# ScopePower.net
KiCad netlist of a schematic drawn in Altium Designer
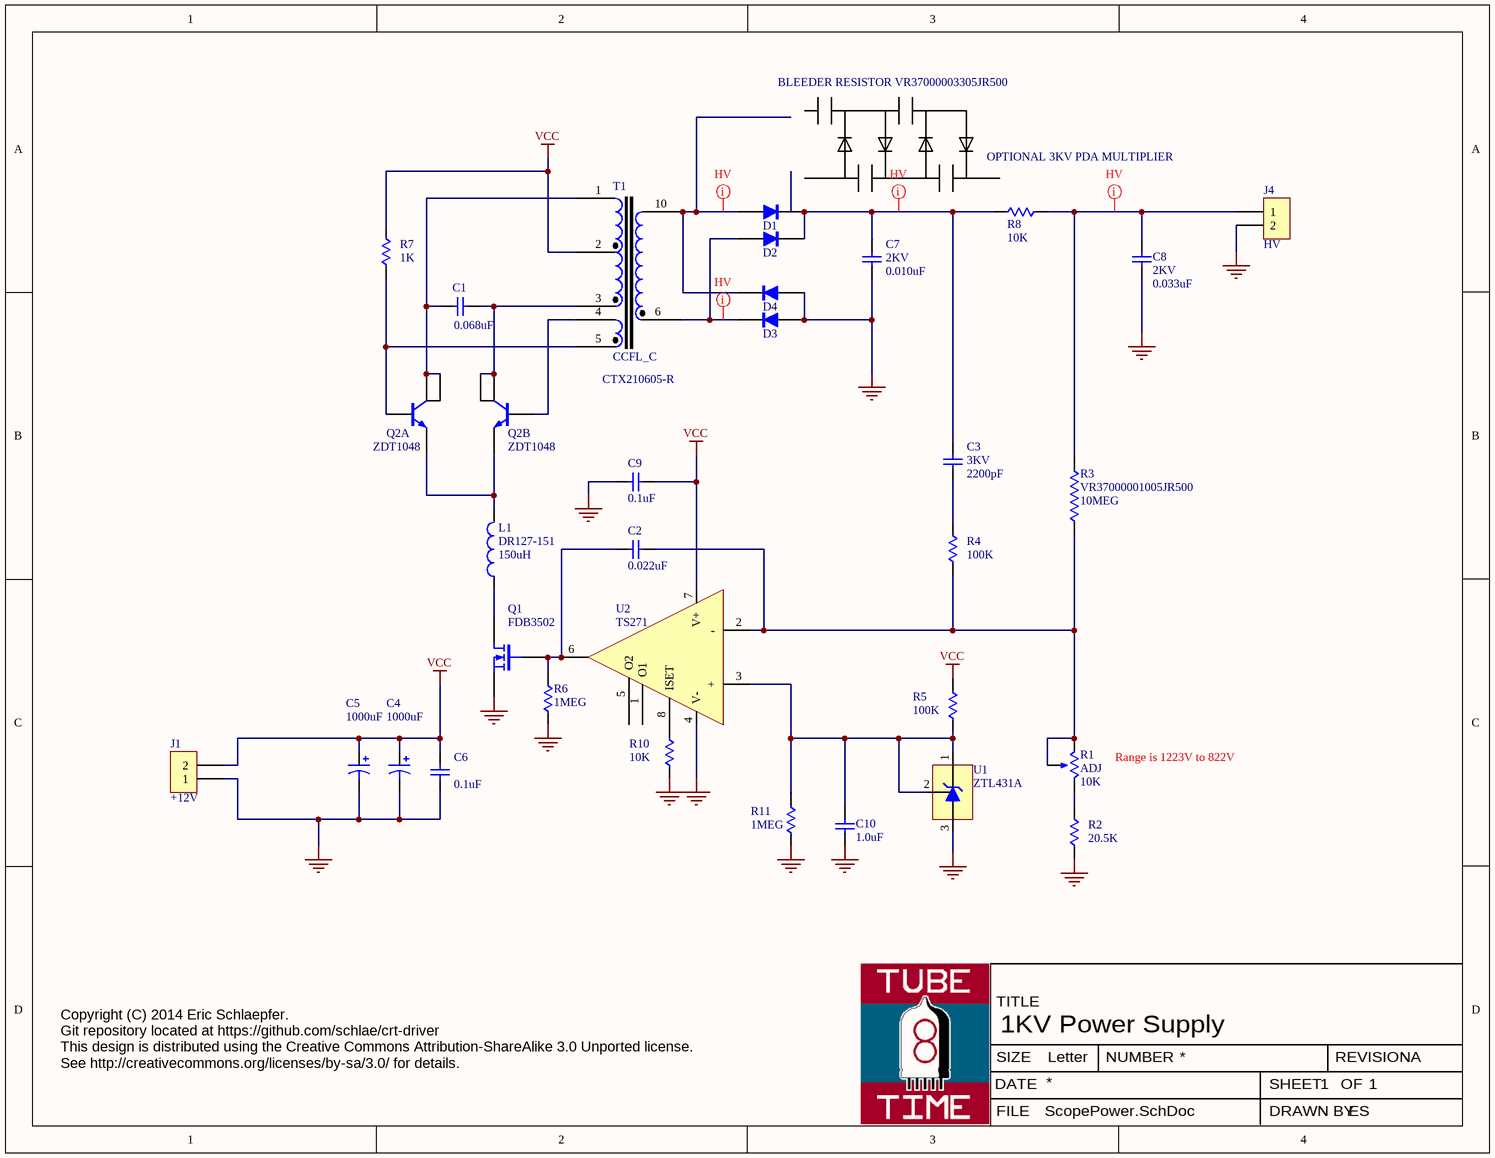
[diagram p0: ScopePower.SchDoc]

(export (version "E")
  (design (tool "Eeschema 10.0.6"))
  (components
    (comp (ref "C1")
      (value "0.068uF")
      (footprint "WIMAMKP2")
      (description "Capacitor")
      (fields (field (name "MANUFPART") "MKP2D026801E00JSSD") (field (name "Comment") "Cap"))
      (libsource (lib "ClikCommon") (part "Cap"))
    )
    (comp (ref "C2")
      (value "0.022uF")
      (footprint "G_0805[2012]")
      (description "Capacitor")
      (libsource (lib "ClikCommon") (part "Cap"))
    )
    (comp (ref "C3")
      (value "3KV")
      (footprint "CAP250X100")
      (description "Capacitor")
      (fields (field (name "ALTIUM_VALUE") "2200pF") (field (name "MANUFPART") "564R30GAD22"))
      (libsource (lib "ClikCommon") (part "Cap"))
    )
    (comp (ref "C4")
      (value "1000uF")
      (footprint "CAP_R200x400")
      (description "Polarized Capacitor")
      (fields (field (name "MANUFPART") "UVR1E102MPD") (field (name "Comment") "Cap Pol2"))
      (libsource (lib "ClikCommon") (part "CapP"))
    )
    (comp (ref "C5")
      (value "1000uF")
      (footprint "CAP_R200x400")
      (description "Polarized Capacitor")
      (fields (field (name "MANUFPART") "UVR1E102MPD") (field (name "Comment") "Cap Pol2"))
      (libsource (lib "ClikCommon") (part "CapP"))
    )
    (comp (ref "C6")
      (value "0.1uF")
      (footprint "G_0805[2012]")
      (description "Capacitor")
      (libsource (lib "ClikCommon") (part "Cap"))
    )
    (comp (ref "C7")
      (value "2KV")
      (footprint "CAP400X100")
      (description "Capacitor")
      (fields (field (name "ALTIUM_VALUE") "0.010uF") (field (name "MANUFPART") "564R20GASS10"))
      (libsource (lib "ClikCommon") (part "Cap"))
    )
    (comp (ref "C8")
      (value "2KV")
      (footprint "CAP400X100")
      (description "Capacitor")
      (fields (field (name "ALTIUM_VALUE") "0.033uF") (field (name "MANUFPART") "565R30GASS33"))
      (libsource (lib "ClikCommon") (part "Cap"))
    )
    (comp (ref "C9")
      (value "0.1uF")
      (footprint "G_0805[2012]")
      (description "Capacitor")
      (libsource (lib "ClikCommon") (part "Cap"))
    )
    (comp (ref "C10")
      (value "1.0uF")
      (footprint "G_0805[2012]")
      (description "Capacitor")
      (fields (field (name "MANUFPART") "C2012X7R1E105K125AB") (field (name "Comment") "Cap"))
      (libsource (lib "ClikCommon") (part "Cap"))
    )
    (comp (ref "D1")
      (value "Diode")
      (footprint "DIODE400X100")
      (fields (field (name "MANUFPART") "rgp02-20e"))
      (libsource (lib "ClikCommon") (part "Diode"))
    )
    (comp (ref "D2")
      (value "Diode")
      (footprint "DIODE400X100")
      (fields (field (name "MANUFPART") "rgp02-20e"))
      (libsource (lib "ClikCommon") (part "Diode"))
    )
    (comp (ref "D3")
      (value "Diode")
      (footprint "DIODE400X100")
      (fields (field (name "MANUFPART") "rgp02-20e"))
      (libsource (lib "") (part "Diode_1"))
    )
    (comp (ref "D4")
      (value "Diode")
      (footprint "DIODE400X100")
      (fields (field (name "MANUFPART") "rgp02-20e"))
      (libsource (lib "") (part "Diode_1"))
    )
    (comp (ref "J1")
      (value "+12V")
      (footprint "HDR2S156")
      (description "Connector, 2 pin")
      (libsource (lib "") (part "CON2_1"))
    )
    (comp (ref "J4")
      (value "HV")
      (footprint "HDR3S156M1")
      (description "Connector, 2 pin")
      (libsource (lib "ClikConnectors") (part "CON2"))
    )
    (comp (ref "L1")
      (value "DR127-151")
      (footprint "DR124")
      (description "Inductor")
      (fields (field (name "ALTIUM_VALUE") "150uH") (field (name "MANUFPART") "DR127-151-R"))
      (libsource (lib "ClikCommon") (part "Inductor"))
    )
    (comp (ref "Q1")
      (value "FDB3502")
      (footprint "G_TO252M[D2PAK]")
      (description "N-Channel MOSFET")
      (libsource (lib "ClikCommon") (part "MOSFET-N"))
    )
    (comp (ref "Q2")
      (value "ZDT1048")
      (footprint "G_SOT223-8")
      (description "NPN Dual Bipolar Transistor")
      (fields (field (name "MANUFPART") "ZDT1048TA"))
      (libsource (lib "ClikCommon") (part "NPN_DUAL"))
    )
    (comp (ref "R1")
      (value "ADJ")
      (footprint "POT_TRIM BOURNS 3386F")
      (description "Variable Resistor")
      (fields (field (name "ALTIUM_VALUE") "10K") (field (name "MANUFPART") "3386F-1-103LF"))
      (libsource (lib "ClikCommon") (part "Pot"))
    )
    (comp (ref "R2")
      (value "20.5K")
      (footprint "G_0805[2012]")
      (description "Resistor")
      (fields (field (name "MANUFPART") "CRCW080520K5FKEA") (field (name "Comment") "Res1"))
      (libsource (lib "ClikCommon") (part "Res"))
    )
    (comp (ref "R3")
      (value "VR37000001005JR500")
      (footprint "RES500X160")
      (description "Resistor, Special Property")
      (fields (field (name "ALTIUM_VALUE") "10MEG"))
      (libsource (lib "ClikCommon") (part "ResSpecial"))
    )
    (comp (ref "R4")
      (value "100K")
      (footprint "G_1206[3216]")
      (description "Resistor")
      (fields (field (name "MANUFPART") "CRCW1206100KFKEA"))
      (libsource (lib "ClikCommon") (part "Res"))
    )
    (comp (ref "R5")
      (value "100K")
      (footprint "G_0805[2012]")
      (description "Resistor")
      (fields (field (name "MANUFPART") "CRCW0805100KFKEA"))
      (libsource (lib "ClikCommon") (part "Res"))
    )
    (comp (ref "R6")
      (value "1MEG")
      (footprint "G_0805[2012]")
      (description "Resistor")
      (fields (field (name "MANUFPART") "CRCW08051M00FKEA"))
      (libsource (lib "ClikCommon") (part "Res"))
    )
    (comp (ref "R7")
      (value "1K")
      (footprint "G_0805[2012]")
      (description "Resistor")
      (fields (field (name "MANUFPART") "CRCW08051K00JNEA") (field (name "Comment") "Res1"))
      (libsource (lib "ClikCommon") (part "Res"))
    )
    (comp (ref "R8")
      (value "10K")
      (footprint "G_1206[3216]")
      (description "Resistor")
      (fields (field (name "MANUFPART") "CRCW120610K0FKEA") (field (name "Comment") "Res1"))
      (libsource (lib "ClikCommon") (part "Res"))
    )
    (comp (ref "R10")
      (value "10K")
      (footprint "G_0805[2012]")
      (description "Resistor")
      (fields (field (name "MANUFPART") "CRCW080510K0FKTA"))
      (libsource (lib "ClikCommon") (part "Res"))
    )
    (comp (ref "R11")
      (value "1MEG")
      (footprint "G_0805[2012]")
      (description "Resistor")
      (fields (field (name "MANUFPART") "CRCW08051M00FKEA"))
      (libsource (lib "ClikCommon") (part "Res"))
    )
    (comp (ref "T1")
      (value "CCFL_C")
      (footprint "CTX2106xx")
      (description "CCFL Transformer")
      (fields (field (name "MANUFPART") "CTX210605-R"))
      (libsource (lib "ClikCommon") (part "CCFL_C"))
    )
    (comp (ref "U1")
      (value "ZTL431A")
      (footprint "G_SOT23")
      (description "Adjustable Shunt Reg")
      (libsource (lib "ClikIC") (part "TL431"))
    )
    (comp (ref "U2")
      (value "TS271")
      (footprint "G_SO8")
      (description "Generic Single Op Amp")
      (fields (field (name "MANUFPART") "TS271IDT"))
      (libsource (lib "ClikIC") (part "OpAmpSingle"))
    )
  )
  (nets
    (net (code "1") (name "GND") (class "Default")
      (node (ref "C10") (pin "1") (pinfunction "1_1") (pintype "passive"))
      (node (ref "C4") (pin "2") (pinfunction "2_2") (pintype "passive"))
      (node (ref "C5") (pin "2") (pinfunction "2_2") (pintype "passive"))
      (node (ref "C6") (pin "2") (pinfunction "2_2") (pintype "passive"))
      (node (ref "C7") (pin "1") (pinfunction "1_1") (pintype "passive"))
      (node (ref "C8") (pin "2") (pinfunction "2_2") (pintype "passive"))
      (node (ref "C9") (pin "2") (pinfunction "2_2") (pintype "passive"))
      (node (ref "D3") (pin "A") (pinfunction "A_A") (pintype "passive"))
      (node (ref "D4") (pin "A") (pinfunction "A_A") (pintype "passive"))
      (node (ref "J1") (pin "1") (pinfunction "1_1") (pintype "passive"))
      (node (ref "J4") (pin "2") (pinfunction "2_2") (pintype "passive"))
      (node (ref "Q1") (pin "S") (pinfunction "S_S") (pintype "passive"))
      (node (ref "R10") (pin "2") (pinfunction "2_2") (pintype "passive"))
      (node (ref "R11") (pin "2") (pinfunction "2_2") (pintype "passive"))
      (node (ref "R2") (pin "1") (pinfunction "1_1") (pintype "passive"))
      (node (ref "R6") (pin "2") (pinfunction "2_2") (pintype "passive"))
      (node (ref "U1") (pin "3") (pinfunction "A_3") (pintype "passive"))
      (node (ref "U2") (pin "4") (pinfunction "V-_4") (pintype "power_in"))
    )
    (net (code "2") (name "Net-(C1-Pad1)") (class "Default")
      (node (ref "C1") (pin "1") (pinfunction "1_1") (pintype "passive"))
      (node (ref "Q2") (pin "5") (pinfunction "C_5") (pintype "passive"))
      (node (ref "Q2") (pin "6") (pinfunction "C_6") (pintype "passive"))
      (node (ref "T1") (pin "1") (pinfunction "1_1") (pintype "passive"))
    )
    (net (code "3") (name "Net-(C1-Pad2)") (class "Default")
      (node (ref "C1") (pin "2") (pinfunction "2_2") (pintype "passive"))
      (node (ref "Q2") (pin "7") (pinfunction "C_7") (pintype "passive"))
      (node (ref "Q2") (pin "8") (pinfunction "C_8") (pintype "passive"))
      (node (ref "T1") (pin "3") (pinfunction "3_3") (pintype "passive"))
    )
    (net (code "4") (name "Net-(C3-Pad1)") (class "Default")
      (node (ref "C3") (pin "1") (pinfunction "1_1") (pintype "passive"))
      (node (ref "R4") (pin "2") (pinfunction "2_2") (pintype "passive"))
    )
    (net (code "5") (name "Net-(C3-Pad2)") (class "Default")
      (node (ref "C3") (pin "2") (pinfunction "2_2") (pintype "passive"))
      (node (ref "C7") (pin "2") (pinfunction "2_2") (pintype "passive"))
      (node (ref "D1") (pin "K") (pinfunction "K_K") (pintype "passive"))
      (node (ref "D2") (pin "K") (pinfunction "K_K") (pintype "passive"))
      (node (ref "R8") (pin "1") (pinfunction "1_1") (pintype "passive"))
    )
    (net (code "6") (name "Net-(C8-Pad1)") (class "Default")
      (node (ref "C8") (pin "1") (pinfunction "1_1") (pintype "passive"))
      (node (ref "J4") (pin "1") (pinfunction "1_1") (pintype "passive"))
      (node (ref "R3") (pin "2") (pinfunction "2_2") (pintype "passive"))
      (node (ref "R8") (pin "2") (pinfunction "2_2") (pintype "passive"))
    )
    (net (code "7") (name "Net-(D1-PadA)") (class "Default")
      (node (ref "D1") (pin "A") (pinfunction "A_A") (pintype "passive"))
      (node (ref "D4") (pin "K") (pinfunction "K_K") (pintype "passive"))
      (node (ref "T1") (pin "10") (pinfunction "10_10") (pintype "passive"))
    )
    (net (code "8") (name "Net-(D2-PadA)") (class "Default")
      (node (ref "D2") (pin "A") (pinfunction "A_A") (pintype "passive"))
      (node (ref "D3") (pin "K") (pinfunction "K_K") (pintype "passive"))
      (node (ref "T1") (pin "6") (pinfunction "6_6") (pintype "passive"))
    )
    (net (code "9") (name "Net-(L1-Pad1)") (class "Default")
      (node (ref "L1") (pin "1") (pinfunction "1_1") (pintype "passive"))
      (node (ref "Q1") (pin "D") (pinfunction "D_D") (pintype "passive"))
    )
    (net (code "10") (name "Net-(Q2A-B)") (class "Default")
      (node (ref "Q2") (pin "4") (pinfunction "B_4") (pintype "passive"))
      (node (ref "R7") (pin "1") (pinfunction "1_1") (pintype "passive"))
      (node (ref "T1") (pin "5") (pinfunction "5_5") (pintype "passive"))
    )
    (net (code "11") (name "Net-(Q2A-E)") (class "Default")
      (node (ref "L1") (pin "2") (pinfunction "2_2") (pintype "passive"))
      (node (ref "Q2") (pin "1") (pinfunction "E_1") (pintype "passive"))
      (node (ref "Q2") (pin "3") (pinfunction "E_3") (pintype "passive"))
    )
    (net (code "12") (name "Net-(Q2B-B)") (class "Default")
      (node (ref "Q2") (pin "2") (pinfunction "B_2") (pintype "passive"))
      (node (ref "T1") (pin "4") (pinfunction "4_4") (pintype "passive"))
    )
    (net (code "13") (name "Net-(R1-BOT)") (class "Default")
      (node (ref "C2") (pin "1") (pinfunction "1_1") (pintype "passive"))
      (node (ref "R1") (pin "2") (pinfunction "BOT_2") (pintype "passive"))
      (node (ref "R1") (pin "3") (pinfunction "TAP_3") (pintype "passive"))
      (node (ref "R3") (pin "1") (pinfunction "1_1") (pintype "passive"))
      (node (ref "R4") (pin "1") (pinfunction "1_1") (pintype "passive"))
      (node (ref "U2") (pin "2") (pinfunction "-_2") (pintype "passive"))
    )
    (net (code "14") (name "Net-(R1-TOP)") (class "Default")
      (node (ref "R1") (pin "1") (pinfunction "TOP_1") (pintype "passive"))
      (node (ref "R2") (pin "2") (pinfunction "2_2") (pintype "passive"))
    )
    (net (code "15") (name "Net-(U1-C)") (class "Default")
      (node (ref "C10") (pin "2") (pinfunction "2_2") (pintype "passive"))
      (node (ref "R11") (pin "1") (pinfunction "1_1") (pintype "passive"))
      (node (ref "R5") (pin "2") (pinfunction "2_2") (pintype "passive"))
      (node (ref "U1") (pin "1") (pinfunction "C_1") (pintype "passive"))
      (node (ref "U1") (pin "2") (pinfunction "REF_2") (pintype "passive"))
      (node (ref "U2") (pin "3") (pinfunction "+_3") (pintype "passive"))
    )
    (net (code "16") (name "Net-(U2-ISET)") (class "Default")
      (node (ref "R10") (pin "1") (pinfunction "1_1") (pintype "passive"))
      (node (ref "U2") (pin "8") (pinfunction "ISET_8") (pintype "passive"))
    )
    (net (code "17") (name "Net-(U2-OUT)") (class "Default")
      (node (ref "C2") (pin "2") (pinfunction "2_2") (pintype "passive"))
      (node (ref "Q1") (pin "G") (pinfunction "G_G") (pintype "passive"))
      (node (ref "R6") (pin "1") (pinfunction "1_1") (pintype "passive"))
      (node (ref "U2") (pin "6") (pinfunction "OUT_6") (pintype "passive"))
    )
    (net (code "18") (name "VCC") (class "Default")
      (node (ref "C4") (pin "1") (pinfunction "1_1") (pintype "passive"))
      (node (ref "C5") (pin "1") (pinfunction "1_1") (pintype "passive"))
      (node (ref "C6") (pin "1") (pinfunction "1_1") (pintype "passive"))
      (node (ref "C9") (pin "1") (pinfunction "1_1") (pintype "passive"))
      (node (ref "J1") (pin "2") (pinfunction "2_2") (pintype "passive"))
      (node (ref "R5") (pin "1") (pinfunction "1_1") (pintype "passive"))
      (node (ref "R7") (pin "2") (pinfunction "2_2") (pintype "passive"))
      (node (ref "T1") (pin "2") (pinfunction "2_2") (pintype "passive"))
      (node (ref "U2") (pin "7") (pinfunction "V+_7") (pintype "power_in"))
    )
    (net (code "19") (name "unconnected-(U2-O1-Pad1)") (class "Default")
      (node (ref "U2") (pin "1") (pinfunction "O1_1") (pintype "passive"))
    )
    (net (code "20") (name "unconnected-(U2-O2-Pad5)") (class "Default")
      (node (ref "U2") (pin "5") (pinfunction "O2_5") (pintype "passive"))
    )
  )
)
